# teamNACHOrev1.net
KiCad netlist of a schematic drawn in EAGLE
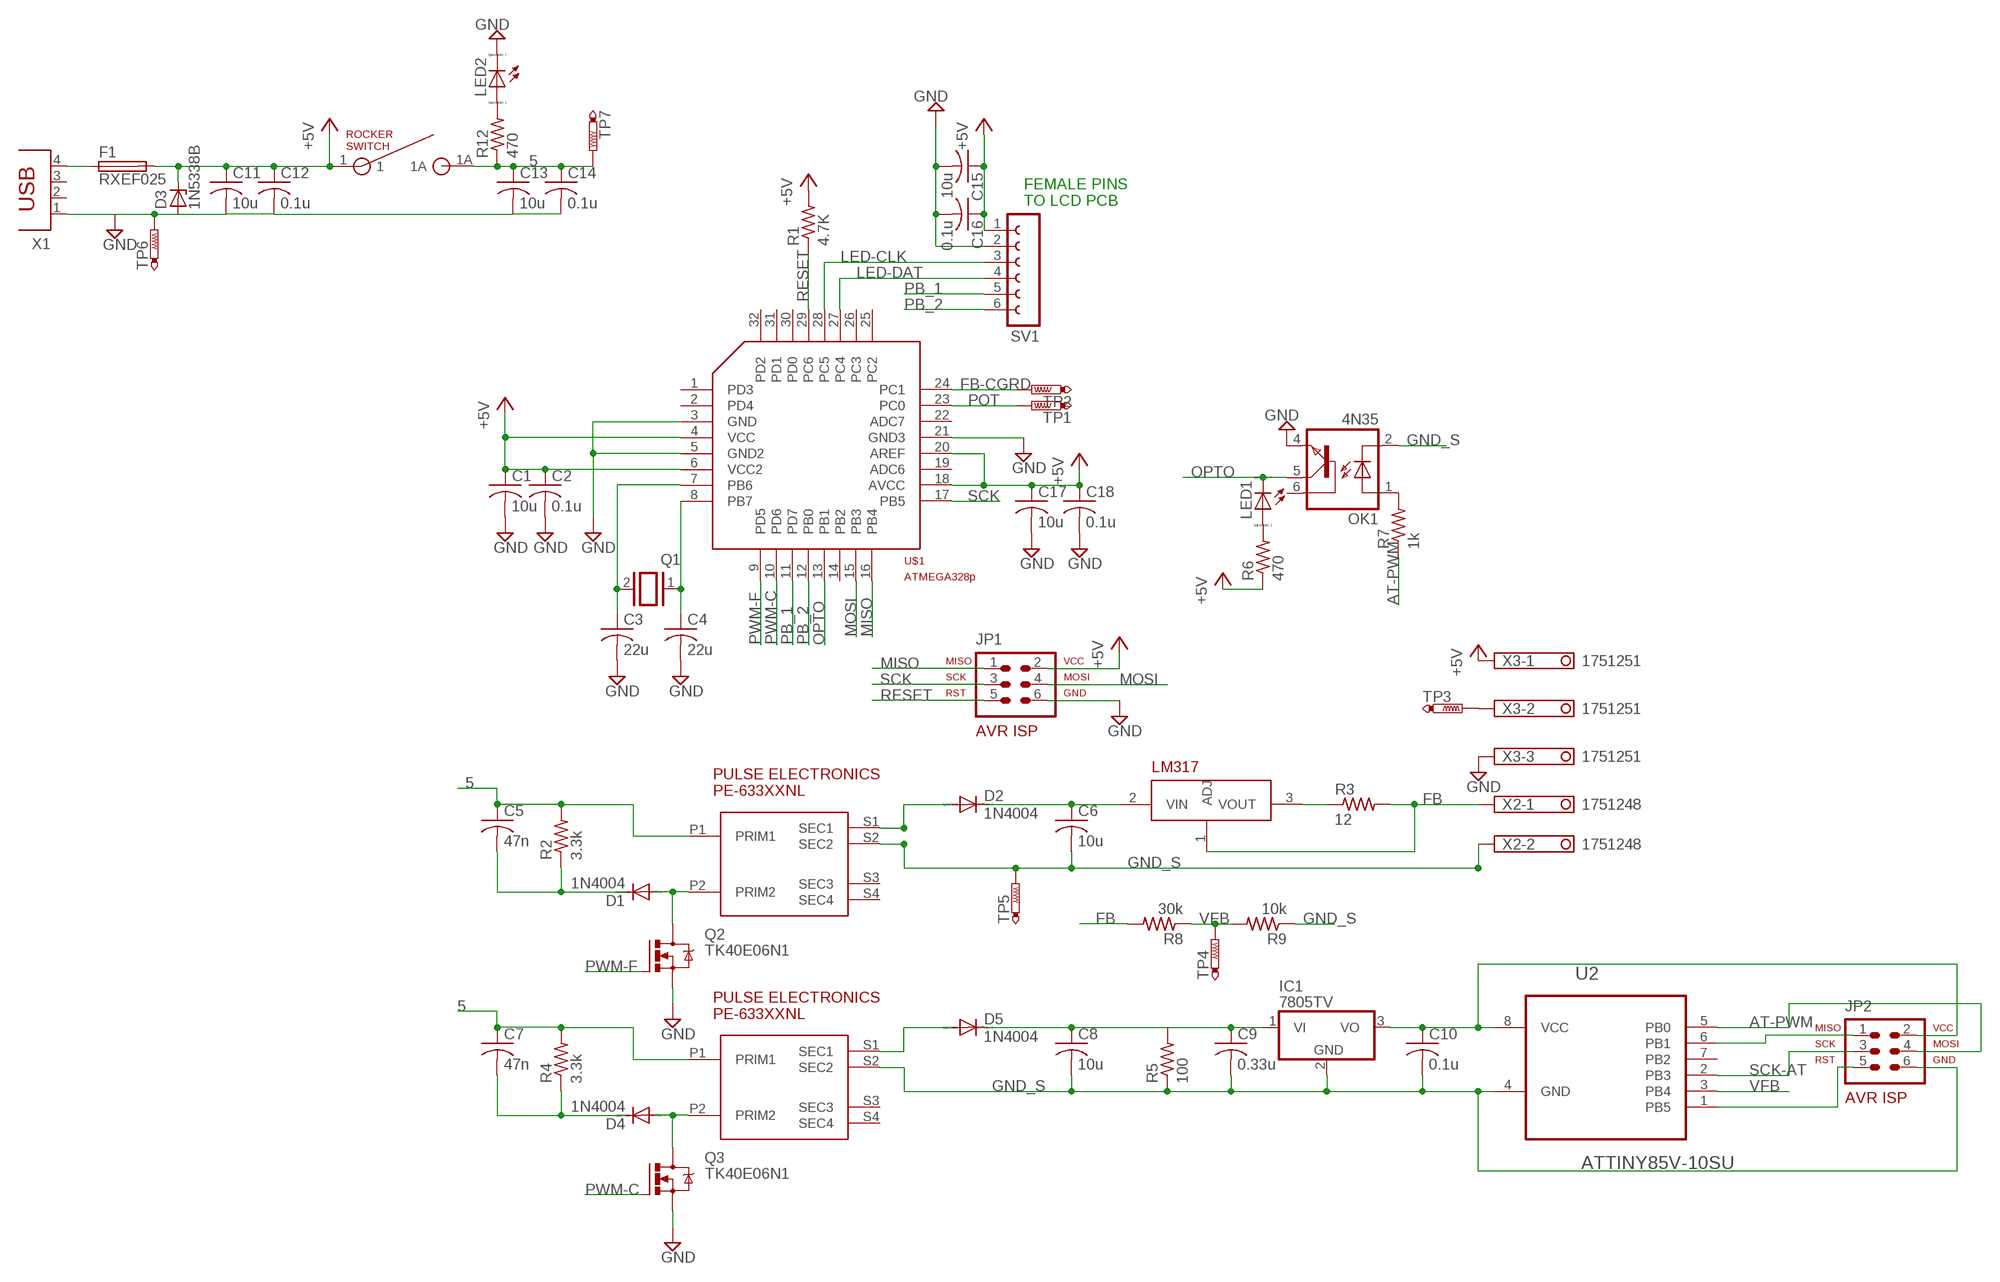
[diagram p0: schematic, sheet 1]

(export (version "E")
  (design (tool "Eeschema 10.0.6"))
  (components
    (comp (ref "C1")
      (value "10u")
      (footprint "eagle-import:C0805")
      (libsource (lib "eagle-import") (part "C-USC0805"))
    )
    (comp (ref "C2")
      (value "0.1u")
      (footprint "eagle-import:C0805")
      (libsource (lib "eagle-import") (part "C-USC0805"))
    )
    (comp (ref "C3")
      (value "22u")
      (footprint "eagle-import:C0805")
      (libsource (lib "eagle-import") (part "C-USC0805"))
    )
    (comp (ref "C4")
      (value "22u")
      (footprint "eagle-import:C0805")
      (libsource (lib "eagle-import") (part "C-USC0805"))
    )
    (comp (ref "C5")
      (value "47n")
      (footprint "eagle-import:C0805")
      (libsource (lib "eagle-import") (part "C-USC0805"))
    )
    (comp (ref "C6")
      (value "10u")
      (footprint "eagle-import:C0805")
      (libsource (lib "eagle-import") (part "C-USC0805"))
    )
    (comp (ref "C7")
      (value "47n")
      (footprint "eagle-import:C0805")
      (libsource (lib "eagle-import") (part "C-USC0805"))
    )
    (comp (ref "C8")
      (value "10u")
      (footprint "eagle-import:C0805")
      (libsource (lib "eagle-import") (part "C-USC0805"))
    )
    (comp (ref "C9")
      (value "0.33u")
      (footprint "eagle-import:C0805")
      (libsource (lib "eagle-import") (part "C-USC0805"))
    )
    (comp (ref "C10")
      (value "0.1u")
      (footprint "eagle-import:C0805")
      (libsource (lib "eagle-import") (part "C-USC0805"))
    )
    (comp (ref "C11")
      (value "10u")
      (footprint "eagle-import:C0805")
      (libsource (lib "eagle-import") (part "C-USC0805"))
    )
    (comp (ref "C12")
      (value "0.1u")
      (footprint "eagle-import:C0805")
      (libsource (lib "eagle-import") (part "C-USC0805"))
    )
    (comp (ref "C13")
      (value "10u")
      (footprint "eagle-import:C0805")
      (libsource (lib "eagle-import") (part "C-USC0805"))
    )
    (comp (ref "C14")
      (value "0.1u")
      (footprint "eagle-import:C0805")
      (libsource (lib "eagle-import") (part "C-USC0805"))
    )
    (comp (ref "C15")
      (value "10u")
      (footprint "eagle-import:C0805")
      (libsource (lib "eagle-import") (part "C-USC0805"))
    )
    (comp (ref "C16")
      (value "0.1u")
      (footprint "eagle-import:C0805")
      (libsource (lib "eagle-import") (part "C-USC0805"))
    )
    (comp (ref "C17")
      (value "10u")
      (footprint "eagle-import:C0805")
      (libsource (lib "eagle-import") (part "C-USC0805"))
    )
    (comp (ref "C18")
      (value "0.1u")
      (footprint "eagle-import:C0805")
      (libsource (lib "eagle-import") (part "C-USC0805"))
    )
    (comp (ref "D1")
      (value "1N4004")
      (footprint "eagle-import:DO41-10")
      (libsource (lib "eagle-import") (part "1N4004"))
    )
    (comp (ref "D2")
      (value "1N4004")
      (footprint "eagle-import:DO41-10")
      (libsource (lib "eagle-import") (part "1N4004"))
    )
    (comp (ref "D3")
      (value "1N5338B")
      (footprint "eagle-import:C1702-15")
      (libsource (lib "eagle-import") (part "1N5333"))
    )
    (comp (ref "D4")
      (value "1N4004")
      (footprint "eagle-import:DO41-10")
      (libsource (lib "eagle-import") (part "1N4004"))
    )
    (comp (ref "D5")
      (value "1N4004")
      (footprint "eagle-import:DO41-10")
      (libsource (lib "eagle-import") (part "1N4004"))
    )
    (comp (ref "F1")
      (value "RXEF025")
      (footprint "eagle-import:PICOFUSE")
      (libsource (lib "eagle-import") (part "FUSEPICOFUSE"))
    )
    (comp (ref "IC1")
      (value "7805TV")
      (footprint "eagle-import:TO220V")
      (libsource (lib "eagle-import") (part "78TV05"))
    )
    (comp (ref "JP1")
      (value "AVR-ISP-6VERT")
      (footprint "eagle-import:AVR-ISP-6")
      (libsource (lib "eagle-import") (part "AVR-ISP-6VERT"))
    )
    (comp (ref "JP2")
      (value "AVR-ISP-6VERT")
      (footprint "eagle-import:AVR-ISP-6")
      (libsource (lib "eagle-import") (part "AVR-ISP-6VERT"))
    )
    (comp (ref "LED1")
      (value "LED_ELD260")
      (footprint "eagle-import:LED_LD260")
      (libsource (lib "eagle-import") (part "LED_ELD260"))
    )
    (comp (ref "LED2")
      (value "LED_ELD260")
      (footprint "eagle-import:LED_LD260")
      (libsource (lib "eagle-import") (part "LED_ELD260"))
    )
    (comp (ref "OK1")
      (value "4N35")
      (footprint "eagle-import:DIL06")
      (fields (field (name "MF") "FAIRCHILD SEMICONDUCTOR"))
      (libsource (lib "eagle-import") (part "4N35"))
    )
    (comp (ref "Q1")
      (value "XTAL/S")
      (footprint "eagle-import:QS")
      (libsource (lib "eagle-import") (part "XTAL/S"))
    )
    (comp (ref "Q2")
      (value "TK40E06N1")
      (footprint "eagle-import:TO220BV")
      (libsource (lib "eagle-import") (part "IRF520"))
    )
    (comp (ref "Q3")
      (value "TK40E06N1")
      (footprint "eagle-import:TO220BV")
      (libsource (lib "eagle-import") (part "IRF520"))
    )
    (comp (ref "R1")
      (value "4.7K")
      (footprint "eagle-import:R0805")
      (libsource (lib "eagle-import") (part "R-US_R0805"))
    )
    (comp (ref "R2")
      (value "3.3k")
      (footprint "eagle-import:R0805")
      (libsource (lib "eagle-import") (part "resistor_R-US_R0805"))
    )
    (comp (ref "R3")
      (value "12")
      (footprint "eagle-import:M0805")
      (libsource (lib "eagle-import") (part "R-US_M0805"))
    )
    (comp (ref "R4")
      (value "3.3k")
      (footprint "eagle-import:R0805")
      (libsource (lib "eagle-import") (part "resistor_R-US_R0805"))
    )
    (comp (ref "R5")
      (value "100")
      (footprint "eagle-import:R0805")
      (libsource (lib "eagle-import") (part "resistor_R-US_R0805"))
    )
    (comp (ref "R6")
      (value "470")
      (footprint "eagle-import:M0805")
      (libsource (lib "eagle-import") (part "R-US_M0805"))
    )
    (comp (ref "R7")
      (value "1k")
      (footprint "eagle-import:M0805")
      (libsource (lib "eagle-import") (part "R-US_M0805"))
    )
    (comp (ref "R8")
      (value "30k")
      (footprint "eagle-import:R0805")
      (libsource (lib "eagle-import") (part "resistor_R-US_R0805"))
    )
    (comp (ref "R9")
      (value "10k")
      (footprint "eagle-import:R0805")
      (libsource (lib "eagle-import") (part "resistor_R-US_R0805"))
    )
    (comp (ref "R12")
      (value "470")
      (footprint "eagle-import:M0805")
      (libsource (lib "eagle-import") (part "R-US_M0805"))
    )
    (comp (ref "SV1")
      (value "FE06-1")
      (footprint "eagle-import:FE06")
      (libsource (lib "eagle-import") (part "FE06-1"))
    )
    (comp (ref "TP1")
      (value "PTR1PAD1-20")
      (footprint "eagle-import:P1-20")
      (libsource (lib "eagle-import") (part "PTR1PAD1-20"))
    )
    (comp (ref "TP2")
      (value "PTR1PAD1-20")
      (footprint "eagle-import:P1-20")
      (libsource (lib "eagle-import") (part "PTR1PAD1-20"))
    )
    (comp (ref "TP3")
      (value "PTR1PAD1-20")
      (footprint "eagle-import:P1-20")
      (libsource (lib "eagle-import") (part "PTR1PAD1-20"))
    )
    (comp (ref "TP4")
      (value "PTR1PAD1-20")
      (footprint "eagle-import:P1-20")
      (libsource (lib "eagle-import") (part "PTR1PAD1-20"))
    )
    (comp (ref "TP5")
      (value "PTR1PAD1-20")
      (footprint "eagle-import:P1-20")
      (libsource (lib "eagle-import") (part "PTR1PAD1-20"))
    )
    (comp (ref "TP6")
      (value "PTR1PAD1-20")
      (footprint "eagle-import:P1-20")
      (libsource (lib "eagle-import") (part "PTR1PAD1-20"))
    )
    (comp (ref "TP7")
      (value "PTR1PAD1-20")
      (footprint "eagle-import:P1-20")
      (libsource (lib "eagle-import") (part "PTR1PAD1-20"))
    )
    (comp (ref "U$1")
      (value "ATMEGA328P")
      (footprint "eagle-import:TQFP32")
      (libsource (lib "eagle-import") (part "ATMEGA328P"))
    )
    (comp (ref "U$2")
      (value "PE-63388NL")
      (footprint "eagle-import:PE-633XXNL")
      (libsource (lib "eagle-import") (part "PE-63388NL"))
    )
    (comp (ref "U$3")
      (value "LM317")
      (footprint "eagle-import:TO220V")
      (libsource (lib "eagle-import") (part "LM317"))
    )
    (comp (ref "U$4")
      (value "COM-08837")
      (footprint "eagle-import:ROCKERSWITCH")
      (libsource (lib "eagle-import") (part "COM-08837"))
    )
    (comp (ref "U$5")
      (value "PE-63388NL")
      (footprint "eagle-import:PE-633XXNL")
      (libsource (lib "eagle-import") (part "PE-63388NL"))
    )
    (comp (ref "U2")
      (value "ATTINY85V-10SU")
      (footprint "eagle-import:SOIC127P798X216-8N")
      (libsource (lib "eagle-import") (part "ATTINY85V-10SU"))
    )
    (comp (ref "X1")
      (value "PN87520")
      (footprint "eagle-import:PN87520")
      (libsource (lib "eagle-import") (part "PN87520"))
    )
    (comp (ref "X2")
      (value "1751248")
      (footprint "eagle-import:1751248")
      (libsource (lib "eagle-import") (part "1751248"))
    )
    (comp (ref "X3")
      (value "1751251")
      (footprint "eagle-import:1751251")
      (libsource (lib "eagle-import") (part "1751251"))
    )
  )
  (nets
    (net (code "1") (name "+5V") (class "Default")
      (node (ref "C1") (pin "1") (pinfunction "1_1") (pintype "passive"))
      (node (ref "C11") (pin "1") (pinfunction "1_1") (pintype "passive"))
      (node (ref "C12") (pin "1") (pinfunction "1_1") (pintype "passive"))
      (node (ref "C15") (pin "1") (pinfunction "1_1") (pintype "passive"))
      (node (ref "C16") (pin "1") (pinfunction "1_1") (pintype "passive"))
      (node (ref "C17") (pin "1") (pinfunction "1_1") (pintype "passive"))
      (node (ref "C18") (pin "1") (pinfunction "1_1") (pintype "passive"))
      (node (ref "C2") (pin "1") (pinfunction "1_1") (pintype "passive"))
      (node (ref "D3") (pin "C") (pinfunction "C_C") (pintype "passive"))
      (node (ref "F1") (pin "2") (pinfunction "2_2") (pintype "passive"))
      (node (ref "JP1") (pin "2") (pinfunction "2_2") (pintype "passive"))
      (node (ref "R1") (pin "2") (pinfunction "2_2") (pintype "passive"))
      (node (ref "R6") (pin "1") (pinfunction "1_1") (pintype "passive"))
      (node (ref "SV1") (pin "1") (pinfunction "1_1") (pintype "passive"))
      (node (ref "U$1") (pin "18") (pinfunction "AVCC_18") (pintype "bidirectional"))
      (node (ref "U$1") (pin "20") (pinfunction "AREF_20") (pintype "bidirectional"))
      (node (ref "U$1") (pin "4") (pinfunction "VCC_4") (pintype "bidirectional"))
      (node (ref "U$1") (pin "6") (pinfunction "VCC2_6") (pintype "bidirectional"))
      (node (ref "U$4") (pin "1") (pinfunction "1_1") (pintype "bidirectional"))
      (node (ref "X3") (pin "1") (pinfunction "K_1") (pintype "passive"))
    )
    (net (code "2") (name "/5") (class "Default")
      (node (ref "C13") (pin "1") (pinfunction "1_1") (pintype "passive"))
      (node (ref "C14") (pin "1") (pinfunction "1_1") (pintype "passive"))
      (node (ref "C5") (pin "1") (pinfunction "1_1") (pintype "passive"))
      (node (ref "C7") (pin "1") (pinfunction "1_1") (pintype "passive"))
      (node (ref "R12") (pin "1") (pinfunction "1_1") (pintype "passive"))
      (node (ref "R2") (pin "2") (pinfunction "2_2") (pintype "passive"))
      (node (ref "R4") (pin "2") (pinfunction "2_2") (pintype "passive"))
      (node (ref "TP7") (pin "TP") (pinfunction "TP_TP") (pintype "input"))
      (node (ref "U$2") (pin "P1") (pinfunction "PRIM1_P1") (pintype "bidirectional"))
      (node (ref "U$4") (pin "1A") (pinfunction "1A_1A") (pintype "bidirectional"))
      (node (ref "U$5") (pin "P1") (pinfunction "PRIM1_P1") (pintype "bidirectional"))
    )
    (net (code "3") (name "/AT-PWM") (class "Default")
      (node (ref "JP2") (pin "4") (pinfunction "4_4") (pintype "passive"))
      (node (ref "R7") (pin "1") (pinfunction "1_1") (pintype "passive"))
      (node (ref "U2") (pin "5") (pinfunction "PB0_5") (pintype "bidirectional"))
    )
    (net (code "4") (name "/FB") (class "Default")
      (node (ref "R3") (pin "2") (pinfunction "2_2") (pintype "passive"))
      (node (ref "R8") (pin "2") (pinfunction "2_2") (pintype "passive"))
      (node (ref "U$3") (pin "1") (pinfunction "ADJ_1") (pintype "bidirectional"))
      (node (ref "X2") (pin "1") (pinfunction "K_1") (pintype "passive"))
    )
    (net (code "5") (name "/FB-CGRD") (class "Default")
      (node (ref "TP2") (pin "TP") (pinfunction "TP_TP") (pintype "input"))
      (node (ref "U$1") (pin "24") (pinfunction "PC1_24") (pintype "bidirectional"))
    )
    (net (code "6") (name "/GND_S") (class "Default")
      (node (ref "C10") (pin "2") (pinfunction "2_2") (pintype "passive"))
      (node (ref "C6") (pin "2") (pinfunction "2_2") (pintype "passive"))
      (node (ref "C8") (pin "2") (pinfunction "2_2") (pintype "passive"))
      (node (ref "C9") (pin "2") (pinfunction "2_2") (pintype "passive"))
      (node (ref "IC1") (pin "2") (pinfunction "GND_2") (pintype "passive"))
      (node (ref "JP2") (pin "6") (pinfunction "6_6") (pintype "passive"))
      (node (ref "OK1") (pin "2") (pinfunction "C_2") (pintype "passive"))
      (node (ref "R5") (pin "1") (pinfunction "1_1") (pintype "passive"))
      (node (ref "R9") (pin "1") (pinfunction "1_1") (pintype "passive"))
      (node (ref "TP5") (pin "TP") (pinfunction "TP_TP") (pintype "input"))
      (node (ref "U$2") (pin "S2") (pinfunction "SEC2_S2") (pintype "bidirectional"))
      (node (ref "U$5") (pin "S2") (pinfunction "SEC2_S2") (pintype "bidirectional"))
      (node (ref "U2") (pin "4") (pinfunction "GND_4") (pintype "passive"))
      (node (ref "X2") (pin "2") (pinfunction "K_2") (pintype "passive"))
    )
    (net (code "7") (name "/LED-CLK") (class "Default")
      (node (ref "SV1") (pin "3") (pinfunction "3_3") (pintype "passive"))
      (node (ref "U$1") (pin "28") (pinfunction "PC5_28") (pintype "bidirectional"))
    )
    (net (code "8") (name "/LED-DAT") (class "Default")
      (node (ref "SV1") (pin "4") (pinfunction "4_4") (pintype "passive"))
      (node (ref "U$1") (pin "27") (pinfunction "PC4_27") (pintype "bidirectional"))
    )
    (net (code "9") (name "/MISO") (class "Default")
      (node (ref "JP1") (pin "1") (pinfunction "1_1") (pintype "passive"))
      (node (ref "U$1") (pin "16") (pinfunction "PB4_16") (pintype "bidirectional"))
    )
    (net (code "10") (name "/MOSI") (class "Default")
      (node (ref "JP1") (pin "4") (pinfunction "4_4") (pintype "passive"))
      (node (ref "U$1") (pin "15") (pinfunction "PB3_15") (pintype "bidirectional"))
    )
    (net (code "11") (name "/OPTO") (class "Default")
      (node (ref "LED1") (pin "K") (pinfunction "C_K") (pintype "passive"))
      (node (ref "OK1") (pin "5") (pinfunction "COL_5") (pintype "passive"))
      (node (ref "U$1") (pin "13") (pinfunction "PB1_13") (pintype "bidirectional"))
    )
    (net (code "12") (name "/PB_1") (class "Default")
      (node (ref "SV1") (pin "5") (pinfunction "5_5") (pintype "passive"))
      (node (ref "U$1") (pin "11") (pinfunction "PD7_11") (pintype "bidirectional"))
    )
    (net (code "13") (name "/PB_2") (class "Default")
      (node (ref "SV1") (pin "6") (pinfunction "6_6") (pintype "passive"))
      (node (ref "U$1") (pin "12") (pinfunction "PB0_12") (pintype "bidirectional"))
    )
    (net (code "14") (name "/POT") (class "Default")
      (node (ref "TP1") (pin "TP") (pinfunction "TP_TP") (pintype "input"))
      (node (ref "U$1") (pin "23") (pinfunction "PC0_23") (pintype "bidirectional"))
    )
    (net (code "15") (name "/PWM-C") (class "Default")
      (node (ref "Q3") (pin "G") (pinfunction "G_G") (pintype "passive"))
      (node (ref "U$1") (pin "10") (pinfunction "PD6_10") (pintype "bidirectional"))
    )
    (net (code "16") (name "/PWM-F") (class "Default")
      (node (ref "Q2") (pin "G") (pinfunction "G_G") (pintype "passive"))
      (node (ref "U$1") (pin "9") (pinfunction "PD5_9") (pintype "bidirectional"))
    )
    (net (code "17") (name "/RESET") (class "Default")
      (node (ref "JP1") (pin "5") (pinfunction "5_5") (pintype "passive"))
      (node (ref "R1") (pin "1") (pinfunction "1_1") (pintype "passive"))
      (node (ref "U$1") (pin "29") (pinfunction "PC6_29") (pintype "bidirectional"))
    )
    (net (code "18") (name "/SCK") (class "Default")
      (node (ref "JP1") (pin "3") (pinfunction "3_3") (pintype "passive"))
      (node (ref "U$1") (pin "17") (pinfunction "PB5_17") (pintype "bidirectional"))
    )
    (net (code "19") (name "/SCK-AT") (class "Default")
      (node (ref "JP2") (pin "3") (pinfunction "3_3") (pintype "passive"))
      (node (ref "U2") (pin "2") (pinfunction "PB3_2") (pintype "bidirectional"))
    )
    (net (code "20") (name "/VFB") (class "Default")
      (node (ref "R8") (pin "1") (pinfunction "1_1") (pintype "passive"))
      (node (ref "R9") (pin "2") (pinfunction "2_2") (pintype "passive"))
      (node (ref "TP4") (pin "TP") (pinfunction "TP_TP") (pintype "input"))
      (node (ref "U2") (pin "3") (pinfunction "PB4_3") (pintype "bidirectional"))
    )
    (net (code "21") (name "GND") (class "Default")
      (node (ref "C1") (pin "2") (pinfunction "2_2") (pintype "passive"))
      (node (ref "C11") (pin "2") (pinfunction "2_2") (pintype "passive"))
      (node (ref "C12") (pin "2") (pinfunction "2_2") (pintype "passive"))
      (node (ref "C13") (pin "2") (pinfunction "2_2") (pintype "passive"))
      (node (ref "C14") (pin "2") (pinfunction "2_2") (pintype "passive"))
      (node (ref "C15") (pin "2") (pinfunction "2_2") (pintype "passive"))
      (node (ref "C16") (pin "2") (pinfunction "2_2") (pintype "passive"))
      (node (ref "C17") (pin "2") (pinfunction "2_2") (pintype "passive"))
      (node (ref "C18") (pin "2") (pinfunction "2_2") (pintype "passive"))
      (node (ref "C2") (pin "2") (pinfunction "2_2") (pintype "passive"))
      (node (ref "C3") (pin "2") (pinfunction "2_2") (pintype "passive"))
      (node (ref "C4") (pin "2") (pinfunction "2_2") (pintype "passive"))
      (node (ref "D3") (pin "A") (pinfunction "A_A") (pintype "passive"))
      (node (ref "JP1") (pin "6") (pinfunction "6_6") (pintype "passive"))
      (node (ref "LED2") (pin "K") (pinfunction "C_K") (pintype "passive"))
      (node (ref "OK1") (pin "4") (pinfunction "EMI_4") (pintype "passive"))
      (node (ref "Q2") (pin "S") (pinfunction "S_S") (pintype "passive"))
      (node (ref "Q3") (pin "S") (pinfunction "S_S") (pintype "passive"))
      (node (ref "SV1") (pin "2") (pinfunction "2_2") (pintype "passive"))
      (node (ref "TP6") (pin "TP") (pinfunction "TP_TP") (pintype "input"))
      (node (ref "U$1") (pin "21") (pinfunction "GND3_21") (pintype "bidirectional"))
      (node (ref "U$1") (pin "3") (pinfunction "GND_3") (pintype "bidirectional"))
      (node (ref "U$1") (pin "5") (pinfunction "GND2_5") (pintype "bidirectional"))
      (node (ref "X1") (pin "1") (pinfunction "1_1") (pintype "passive"))
      (node (ref "X3") (pin "3") (pinfunction "K_3") (pintype "passive"))
    )
    (net (code "22") (name "Net-(C5-Pad2)") (class "Default")
      (node (ref "C5") (pin "2") (pinfunction "2_2") (pintype "passive"))
      (node (ref "D1") (pin "C") (pinfunction "C_C") (pintype "passive"))
      (node (ref "R2") (pin "1") (pinfunction "1_1") (pintype "passive"))
    )
    (net (code "23") (name "Net-(C7-Pad2)") (class "Default")
      (node (ref "C7") (pin "2") (pinfunction "2_2") (pintype "passive"))
      (node (ref "D4") (pin "C") (pinfunction "C_C") (pintype "passive"))
      (node (ref "R4") (pin "1") (pinfunction "1_1") (pintype "passive"))
    )
    (net (code "24") (name "Net-(F1-Pad1)") (class "Default")
      (node (ref "F1") (pin "1") (pinfunction "1_1") (pintype "passive"))
      (node (ref "X1") (pin "4") (pinfunction "4_4") (pintype "passive"))
    )
    (net (code "25") (name "Net-(IC1-VI)") (class "Default")
      (node (ref "C8") (pin "1") (pinfunction "1_1") (pintype "passive"))
      (node (ref "C9") (pin "1") (pinfunction "1_1") (pintype "passive"))
      (node (ref "D5") (pin "C") (pinfunction "C_C") (pintype "passive"))
      (node (ref "IC1") (pin "1") (pinfunction "VI_1") (pintype "input"))
      (node (ref "R5") (pin "2") (pinfunction "2_2") (pintype "passive"))
    )
    (net (code "26") (name "Net-(IC1-VO)") (class "Default")
      (node (ref "C10") (pin "1") (pinfunction "1_1") (pintype "passive"))
      (node (ref "IC1") (pin "3") (pinfunction "VO_3") (pintype "passive"))
      (node (ref "JP2") (pin "2") (pinfunction "2_2") (pintype "passive"))
      (node (ref "U2") (pin "8") (pinfunction "VCC_8") (pintype "power_in"))
    )
    (net (code "27") (name "Net-(LED1-PadA)") (class "Default")
      (node (ref "LED1") (pin "A") (pinfunction "A_A") (pintype "passive"))
      (node (ref "R6") (pin "2") (pinfunction "2_2") (pintype "passive"))
    )
    (net (code "28") (name "Net-(LED2-PadA)") (class "Default")
      (node (ref "LED2") (pin "A") (pinfunction "A_A") (pintype "passive"))
      (node (ref "R12") (pin "2") (pinfunction "2_2") (pintype "passive"))
    )
    (net (code "29") (name "Net-(OK1-A)") (class "Default")
      (node (ref "OK1") (pin "1") (pinfunction "A_1") (pintype "passive"))
      (node (ref "R7") (pin "2") (pinfunction "2_2") (pintype "passive"))
    )
    (net (code "30") (name "Net-(U$1-PB6)") (class "Default")
      (node (ref "C3") (pin "1") (pinfunction "1_1") (pintype "passive"))
      (node (ref "Q1") (pin "2") (pinfunction "2_2") (pintype "passive"))
      (node (ref "U$1") (pin "7") (pinfunction "PB6_7") (pintype "bidirectional"))
    )
    (net (code "31") (name "Net-(U$1-PB7)") (class "Default")
      (node (ref "C4") (pin "1") (pinfunction "1_1") (pintype "passive"))
      (node (ref "Q1") (pin "1") (pinfunction "1_1") (pintype "passive"))
      (node (ref "U$1") (pin "8") (pinfunction "PB7_8") (pintype "bidirectional"))
    )
    (net (code "32") (name "Net-(U$2-PRIM2)") (class "Default")
      (node (ref "D1") (pin "A") (pinfunction "A_A") (pintype "passive"))
      (node (ref "Q2") (pin "D") (pinfunction "D_D") (pintype "passive"))
      (node (ref "U$2") (pin "P2") (pinfunction "PRIM2_P2") (pintype "bidirectional"))
    )
    (net (code "33") (name "Net-(U$2-SEC1)") (class "Default")
      (node (ref "D2") (pin "A") (pinfunction "A_A") (pintype "passive"))
      (node (ref "U$2") (pin "S1") (pinfunction "SEC1_S1") (pintype "bidirectional"))
    )
    (net (code "34") (name "Net-(U$3-VIN)") (class "Default")
      (node (ref "C6") (pin "1") (pinfunction "1_1") (pintype "passive"))
      (node (ref "D2") (pin "C") (pinfunction "C_C") (pintype "passive"))
      (node (ref "U$3") (pin "2") (pinfunction "VIN_2") (pintype "bidirectional"))
    )
    (net (code "35") (name "Net-(U$3-VOUT)") (class "Default")
      (node (ref "R3") (pin "1") (pinfunction "1_1") (pintype "passive"))
      (node (ref "U$3") (pin "3") (pinfunction "VOUT_3") (pintype "bidirectional"))
    )
    (net (code "36") (name "Net-(U$5-PRIM2)") (class "Default")
      (node (ref "D4") (pin "A") (pinfunction "A_A") (pintype "passive"))
      (node (ref "Q3") (pin "D") (pinfunction "D_D") (pintype "passive"))
      (node (ref "U$5") (pin "P2") (pinfunction "PRIM2_P2") (pintype "bidirectional"))
    )
    (net (code "37") (name "Net-(U$5-SEC1)") (class "Default")
      (node (ref "D5") (pin "A") (pinfunction "A_A") (pintype "passive"))
      (node (ref "U$5") (pin "S1") (pinfunction "SEC1_S1") (pintype "bidirectional"))
    )
    (net (code "38") (name "Net-(U2-PB1)") (class "Default")
      (node (ref "JP2") (pin "1") (pinfunction "1_1") (pintype "passive"))
      (node (ref "U2") (pin "6") (pinfunction "PB1_6") (pintype "bidirectional"))
    )
    (net (code "39") (name "Net-(U2-PB5)") (class "Default")
      (node (ref "JP2") (pin "5") (pinfunction "5_5") (pintype "passive"))
      (node (ref "U2") (pin "1") (pinfunction "PB5_1") (pintype "bidirectional"))
    )
    (net (code "40") (name "Net-(X3B-K)") (class "Default")
      (node (ref "TP3") (pin "TP") (pinfunction "TP_TP") (pintype "input"))
      (node (ref "X3") (pin "2") (pinfunction "K_2") (pintype "passive"))
    )
    (net (code "41") (name "unconnected-(OK1-BAS-Pad6)") (class "Default")
      (node (ref "OK1") (pin "6") (pinfunction "BAS_6") (pintype "passive"))
    )
    (net (code "42") (name "unconnected-(U$1-ADC6-Pad19)") (class "Default")
      (node (ref "U$1") (pin "19") (pinfunction "ADC6_19") (pintype "bidirectional"))
    )
    (net (code "43") (name "unconnected-(U$1-ADC7-Pad22)") (class "Default")
      (node (ref "U$1") (pin "22") (pinfunction "ADC7_22") (pintype "bidirectional"))
    )
    (net (code "44") (name "unconnected-(U$1-PB2-Pad14)") (class "Default")
      (node (ref "U$1") (pin "14") (pinfunction "PB2_14") (pintype "bidirectional"))
    )
    (net (code "45") (name "unconnected-(U$1-PC2-Pad25)") (class "Default")
      (node (ref "U$1") (pin "25") (pinfunction "PC2_25") (pintype "bidirectional"))
    )
    (net (code "46") (name "unconnected-(U$1-PC3-Pad26)") (class "Default")
      (node (ref "U$1") (pin "26") (pinfunction "PC3_26") (pintype "bidirectional"))
    )
    (net (code "47") (name "unconnected-(U$1-PD0-Pad30)") (class "Default")
      (node (ref "U$1") (pin "30") (pinfunction "PD0_30") (pintype "bidirectional"))
    )
    (net (code "48") (name "unconnected-(U$1-PD1-Pad31)") (class "Default")
      (node (ref "U$1") (pin "31") (pinfunction "PD1_31") (pintype "bidirectional"))
    )
    (net (code "49") (name "unconnected-(U$1-PD2-Pad32)") (class "Default")
      (node (ref "U$1") (pin "32") (pinfunction "PD2_32") (pintype "bidirectional"))
    )
    (net (code "50") (name "unconnected-(U$1-PD3-Pad1)") (class "Default")
      (node (ref "U$1") (pin "1") (pinfunction "PD3_1") (pintype "bidirectional"))
    )
    (net (code "51") (name "unconnected-(U$1-PD4-Pad2)") (class "Default")
      (node (ref "U$1") (pin "2") (pinfunction "PD4_2") (pintype "bidirectional"))
    )
    (net (code "52") (name "unconnected-(U$2-SEC3-PadS3)") (class "Default")
      (node (ref "U$2") (pin "S3") (pinfunction "SEC3_S3") (pintype "bidirectional"))
    )
    (net (code "53") (name "unconnected-(U$2-SEC4-PadS4)") (class "Default")
      (node (ref "U$2") (pin "S4") (pinfunction "SEC4_S4") (pintype "bidirectional"))
    )
    (net (code "54") (name "unconnected-(U$5-SEC3-PadS3)") (class "Default")
      (node (ref "U$5") (pin "S3") (pinfunction "SEC3_S3") (pintype "bidirectional"))
    )
    (net (code "55") (name "unconnected-(U$5-SEC4-PadS4)") (class "Default")
      (node (ref "U$5") (pin "S4") (pinfunction "SEC4_S4") (pintype "bidirectional"))
    )
    (net (code "56") (name "unconnected-(U2-PB2-Pad7)") (class "Default")
      (node (ref "U2") (pin "7") (pinfunction "PB2_7") (pintype "bidirectional"))
    )
    (net (code "57") (name "unconnected-(X1-Pad2)") (class "Default")
      (node (ref "X1") (pin "2") (pinfunction "2_2") (pintype "passive"))
    )
    (net (code "58") (name "unconnected-(X1-Pad3)") (class "Default")
      (node (ref "X1") (pin "3") (pinfunction "3_3") (pintype "passive"))
    )
  )
)
